# pi3_hat.net
KiCad netlist of a schematic drawn in EAGLE
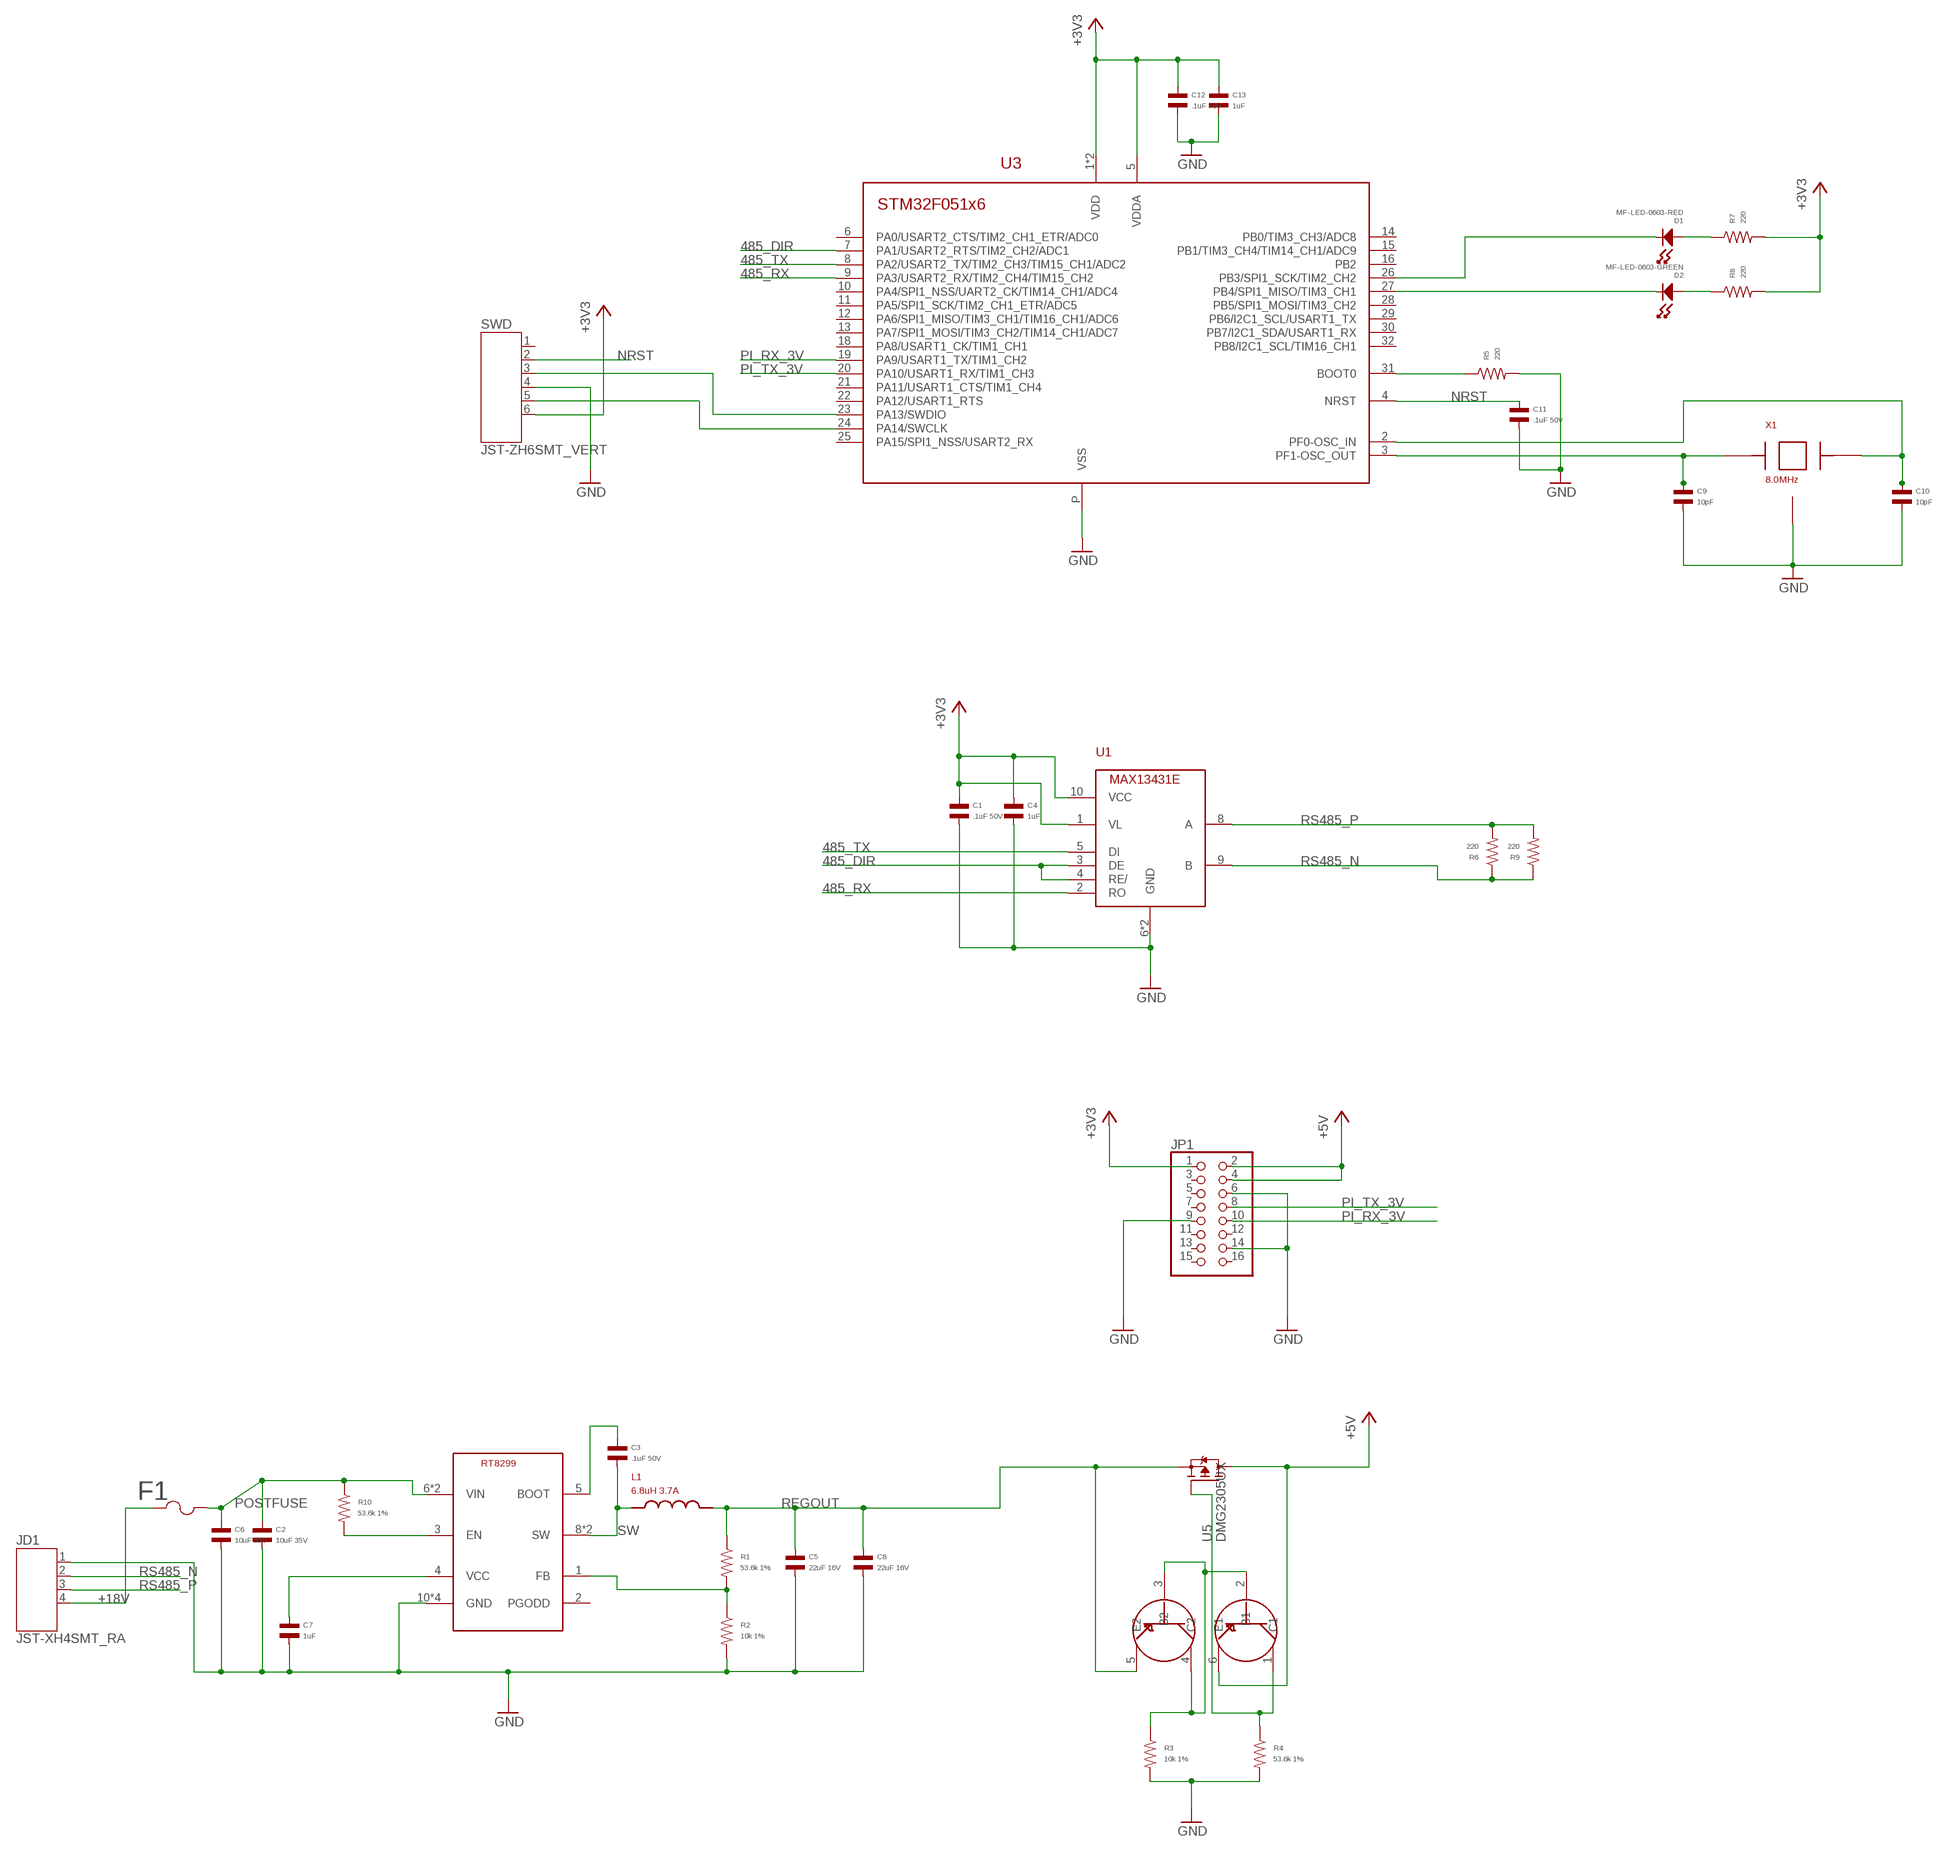
[diagram p0: schematic, sheet 1]

(export (version "E")
  (design (tool "Eeschema 10.0.6"))
  (components
    (comp (ref "C1")
      (value ".1uF 50V")
      (footprint "eagle-import:C0805")
      (fields (field (name "HOUSEPART") "1") (field (name "MPN") "MF-CAP-0805-0.1uF"))
      (libsource (lib "eagle-import") (part "CAPACITOR_NP_0805"))
    )
    (comp (ref "C2")
      (value "10uF 35V")
      (footprint "eagle-import:C1206")
      (fields (field (name "MF") "TDK") (field (name "MPN") "CGA5L1X7R1V106K160AC"))
      (libsource (lib "eagle-import") (part "CAPACITOR_NP_1206"))
    )
    (comp (ref "C3")
      (value ".1uF 50V")
      (footprint "eagle-import:C0805")
      (fields (field (name "HOUSEPART") "1") (field (name "MPN") "MF-CAP-0805-0.1uF"))
      (libsource (lib "eagle-import") (part "CAPACITOR_NP_0805"))
    )
    (comp (ref "C4")
      (value "1uF")
      (footprint "eagle-import:C0603")
      (fields (field (name "HOUSEPART") "1") (field (name "MPN") "MF-CAP-0603-1uF"))
      (libsource (lib "eagle-import") (part "CAPACITOR_NP_0603"))
    )
    (comp (ref "C5")
      (value "22uF 16V")
      (footprint "eagle-import:C1210")
      (fields (field (name "MF") "SAMSUNG") (field (name "MPN") "CL32A226KOJNNNE"))
      (libsource (lib "eagle-import") (part "CAPACITOR_NP_1210"))
    )
    (comp (ref "C6")
      (value "10uF 35V")
      (footprint "eagle-import:C1206")
      (fields (field (name "MF") "TDK") (field (name "MPN") "CGA5L1X7R1V106K160AC"))
      (libsource (lib "eagle-import") (part "CAPACITOR_NP_1206"))
    )
    (comp (ref "C7")
      (value "1uF")
      (footprint "eagle-import:C0603")
      (fields (field (name "HOUSEPART") "1") (field (name "MPN") "MF-CAP-0603-1uF"))
      (libsource (lib "eagle-import") (part "CAPACITOR_NP_0603"))
    )
    (comp (ref "C8")
      (value "22uF 16V")
      (footprint "eagle-import:C1210")
      (fields (field (name "MF") "SAMSUNG") (field (name "MPN") "CL32A226KOJNNNE"))
      (libsource (lib "eagle-import") (part "CAPACITOR_NP_1210"))
    )
    (comp (ref "C9")
      (value "10pF")
      (footprint "eagle-import:C0603")
      (fields
        (field (name "HOUSEPART") "1")
        (field (name "MF") "MACROFAB")
        (field (name "MPN") "MF-CAP-0603-10pF")
      )
      (libsource (lib "eagle-import") (part "CAPACITOR_NP_0603"))
    )
    (comp (ref "C10")
      (value "10pF")
      (footprint "eagle-import:C0603")
      (fields
        (field (name "HOUSEPART") "1")
        (field (name "MF") "MACROFAB")
        (field (name "MPN") "MF-CAP-0603-10pF")
      )
      (libsource (lib "eagle-import") (part "CAPACITOR_NP_0603"))
    )
    (comp (ref "C11")
      (value ".1uF 50V")
      (footprint "eagle-import:C0805")
      (fields (field (name "HOUSEPART") "1") (field (name "MPN") "MF-CAP-0805-0.1uF"))
      (libsource (lib "eagle-import") (part "CAPACITOR_NP_0805"))
    )
    (comp (ref "C12")
      (value ".1uF 50V")
      (footprint "eagle-import:C0805")
      (fields (field (name "HOUSEPART") "1") (field (name "MPN") "MF-CAP-0805-0.1uF"))
      (libsource (lib "eagle-import") (part "CAPACITOR_NP_0805"))
    )
    (comp (ref "C13")
      (value "1uF")
      (footprint "eagle-import:C0603")
      (fields (field (name "HOUSEPART") "1") (field (name "MPN") "MF-CAP-0603-1uF"))
      (libsource (lib "eagle-import") (part "CAPACITOR_NP_0603"))
    )
    (comp (ref "D1")
      (value "MF-LED-0603-RED")
      (footprint "eagle-import:LED0603")
      (fields (field (name "HOUSEPART") "YES"))
      (libsource (lib "eagle-import") (part "LED_SINGLE-0603-RED"))
    )
    (comp (ref "D2")
      (value "MF-LED-0603-GREEN")
      (footprint "eagle-import:LED0603")
      (fields (field (name "HOUSEPART") "YES"))
      (libsource (lib "eagle-import") (part "LED_SINGLE-0603-GREEN"))
    )
    (comp (ref "F1")
      (value "MFU0603FF04000P100")
      (footprint "eagle-import:FUS_VISHAY_MFU0603")
      (libsource (lib "eagle-import") (part "MFU0603FF04000P100"))
    )
    (comp (ref "JD1")
      (value "JST-XH4SMT_RA")
      (footprint "eagle-import:JST_XH_SMT_RA_4")
      (fields (field (name "MF") "JST") (field (name "MPN") "S4B-XH-SM4-TB(LF)(SN)"))
      (libsource (lib "eagle-import") (part "JST-XH4SMT_RA"))
    )
    (comp (ref "JP1")
      (value "PINHD-2X8")
      (footprint "eagle-import:2X08")
      (libsource (lib "eagle-import") (part "PINHD-2X8"))
    )
    (comp (ref "L1")
      (value "6.8uH 3.7A")
      (footprint "eagle-import:TAIYO_8040")
      (fields
        (field (name "HOUSEPART") "0")
        (field (name "MF") "TAIYO YUDEN")
        (field (name "MPN") "NR8040T6R8N")
      )
      (libsource (lib "eagle-import") (part "INDUCTORTAIYO_8040"))
    )
    (comp (ref "R1")
      (value "53.6k 1%")
      (footprint "eagle-import:R0603")
      (fields (field (name "MF") "Panasonic") (field (name "MPN") "ERJ-3EKF5362V"))
      (libsource (lib "eagle-import") (part "RESISTOR_0603"))
    )
    (comp (ref "R2")
      (value "10k 1%")
      (footprint "eagle-import:R0603")
      (fields (field (name "MF") "Panasonic") (field (name "MPN") "ERJ-3EKF1002V"))
      (libsource (lib "eagle-import") (part "RESISTOR_0603"))
    )
    (comp (ref "R3")
      (value "10k 1%")
      (footprint "eagle-import:R0603")
      (fields (field (name "MF") "Panasonic") (field (name "MPN") "ERJ-3EKF1002V"))
      (libsource (lib "eagle-import") (part "RESISTOR_0603"))
    )
    (comp (ref "R4")
      (value "53.6k 1%")
      (footprint "eagle-import:R0603")
      (fields (field (name "MF") "Panasonic") (field (name "MPN") "ERJ-3EKF5362V"))
      (libsource (lib "eagle-import") (part "RESISTOR_0603"))
    )
    (comp (ref "R5")
      (value "220")
      (footprint "eagle-import:R0603")
      (fields (field (name "MPN") "MF-RES-0603-220"))
      (libsource (lib "eagle-import") (part "RESISTOR_0603"))
    )
    (comp (ref "R6")
      (value "220")
      (footprint "eagle-import:R0603")
      (fields (field (name "MPN") "MF-RES-0603-220"))
      (libsource (lib "eagle-import") (part "RESISTOR_0603"))
    )
    (comp (ref "R7")
      (value "220")
      (footprint "eagle-import:R0603")
      (fields (field (name "MPN") "MF-RES-0603-220"))
      (libsource (lib "eagle-import") (part "RESISTOR_0603"))
    )
    (comp (ref "R8")
      (value "220")
      (footprint "eagle-import:R0603")
      (fields (field (name "MPN") "MF-RES-0603-220"))
      (libsource (lib "eagle-import") (part "RESISTOR_0603"))
    )
    (comp (ref "R9")
      (value "220")
      (footprint "eagle-import:R0603")
      (fields (field (name "MPN") "MF-RES-0603-220"))
      (libsource (lib "eagle-import") (part "RESISTOR_0603"))
    )
    (comp (ref "R10")
      (value "53.6k 1%")
      (footprint "eagle-import:R0603")
      (fields (field (name "MF") "Panasonic") (field (name "MPN") "ERJ-3EKF5362V"))
      (libsource (lib "eagle-import") (part "RESISTOR_0603"))
    )
    (comp (ref "SWD")
      (value "JST-ZH6SMT_VERT")
      (footprint "eagle-import:JST_B6B-ZR-SM4-TF(LF)(SN)")
      (fields (field (name "MF") "JST") (field (name "MPN") "B6B-ZR-SM4-TF(LF)(SN)"))
      (libsource (lib "eagle-import") (part "JST-ZH6SMT_VERT"))
    )
    (comp (ref "U1")
      (value "MAX13431E")
      (footprint "eagle-import:TDFN10")
      (fields (field (name "MF") "Maxim") (field (name "MPN") "MAX13431EETB+T"))
      (libsource (lib "eagle-import") (part "MAX13431E"))
    )
    (comp (ref "U2")
      (value "RT829910L_DFN")
      (footprint "eagle-import:10L_DFN")
      (fields (field (name "MF") "Richtek") (field (name "MPN") "RT8299ZQW"))
      (libsource (lib "eagle-import") (part "RT829910L_DFN"))
    )
    (comp (ref "U3")
      (value "STM32F051X6UFQFPN32")
      (footprint "eagle-import:UFQFPN32")
      (fields (field (name "MF") "STMicroelectronics") (field (name "MPN") "STM32F051K6U6"))
      (libsource (lib "eagle-import") (part "STM32F051X6UFQFPN32"))
    )
    (comp (ref "U4")
      (value "DMMT5401")
      (footprint "eagle-import:SOT26")
      (fields (field (name "MF") "Didoes Incorporated") (field (name "MPN") "DMMT5401-7-F"))
      (libsource (lib "eagle-import") (part "DMMT5401"))
    )
    (comp (ref "U5")
      (value "DMG2305UX")
      (footprint "eagle-import:SOT23")
      (fields (field (name "MF") "Diodes Incorporated") (field (name "MPN") "DMG2305UX-13"))
      (libsource (lib "eagle-import") (part "DMG2305UX"))
    )
    (comp (ref "X1")
      (value "8.0MHz")
      (footprint "eagle-import:ABM3B")
      (fields (field (name "MF") "Abracon") (field (name "MPN") "ABM3B-8.000MHZ-10-1-U-T"))
      (libsource (lib "eagle-import") (part "CRYSTALABM3B"))
    )
  )
  (nets
    (net (code "1") (name "+3V3") (class "Default")
      (node (ref "C1") (pin "P$1") (pinfunction "P$1_P$1") (pintype "passive"))
      (node (ref "C12") (pin "P$1") (pinfunction "P$1_P$1") (pintype "passive"))
      (node (ref "C13") (pin "P$1") (pinfunction "P$1_P$1") (pintype "passive"))
      (node (ref "C4") (pin "P$1") (pinfunction "P$1_P$1") (pintype "passive"))
      (node (ref "JP1") (pin "1") (pinfunction "1_1") (pintype "passive"))
      (node (ref "R7") (pin "P$2") (pinfunction "P$2_P$2") (pintype "passive"))
      (node (ref "R8") (pin "P$2") (pinfunction "P$2_P$2") (pintype "passive"))
      (node (ref "SWD") (pin "6") (pinfunction "6_6") (pintype "passive"))
      (node (ref "U1") (pin "1") (pinfunction "VL_1") (pintype "bidirectional"))
      (node (ref "U1") (pin "10") (pinfunction "VCC_10") (pintype "bidirectional"))
      (node (ref "U3") (pin "1") (pinfunction "VDD_1") (pintype "bidirectional"))
      (node (ref "U3") (pin "17") (pinfunction "VDD_17") (pintype "bidirectional"))
      (node (ref "U3") (pin "5") (pinfunction "VDDA_5") (pintype "bidirectional"))
    )
    (net (code "2") (name "+5V") (class "Default")
      (node (ref "JP1") (pin "2") (pinfunction "2_2") (pintype "passive"))
      (node (ref "JP1") (pin "4") (pinfunction "4_4") (pintype "passive"))
      (node (ref "U4") (pin "6") (pinfunction "E1_6") (pintype "bidirectional"))
      (node (ref "U5") (pin "3") (pinfunction "D_3") (pintype "passive"))
    )
    (net (code "3") (name "/+18V") (class "Default")
      (node (ref "F1") (pin "1") (pinfunction "1_1") (pintype "passive"))
      (node (ref "JD1") (pin "4") (pinfunction "4_4") (pintype "passive"))
    )
    (net (code "4") (name "/485_DIR") (class "Default")
      (node (ref "U1") (pin "3") (pinfunction "DE_3") (pintype "bidirectional"))
      (node (ref "U1") (pin "4") (pinfunction "RE/_4") (pintype "bidirectional"))
      (node (ref "U3") (pin "7") (pinfunction "PA1/USART2_RTS/TIM2_CH2/ADC1_7") (pintype "bidirectional"))
    )
    (net (code "5") (name "/485_RX") (class "Default")
      (node (ref "U1") (pin "2") (pinfunction "RO_2") (pintype "bidirectional"))
      (node (ref "U3") (pin "9") (pinfunction "PA3/USART2_RX/TIM2_CH4/TIM15_CH2_9") (pintype "bidirectional"))
    )
    (net (code "6") (name "/485_TX") (class "Default")
      (node (ref "U1") (pin "5") (pinfunction "DI_5") (pintype "bidirectional"))
      (node (ref "U3") (pin "8") (pinfunction "PA2/USART2_TX/TIM2_CH3/TIM15_CH1/ADC2_8") (pintype "bidirectional"))
    )
    (net (code "7") (name "/NRST") (class "Default")
      (node (ref "C11") (pin "P$1") (pinfunction "P$1_P$1") (pintype "passive"))
      (node (ref "SWD") (pin "2") (pinfunction "2_2") (pintype "passive"))
      (node (ref "U3") (pin "4") (pinfunction "NRST_4") (pintype "bidirectional"))
    )
    (net (code "8") (name "/PI_RX_3V") (class "Default")
      (node (ref "JP1") (pin "10") (pinfunction "10_10") (pintype "passive"))
      (node (ref "U3") (pin "19") (pinfunction "PA9/USART1_TX/TIM1_CH2_19") (pintype "bidirectional"))
    )
    (net (code "9") (name "/PI_TX_3V") (class "Default")
      (node (ref "JP1") (pin "8") (pinfunction "8_8") (pintype "passive"))
      (node (ref "U3") (pin "20") (pinfunction "PA10/USART1_RX/TIM1_CH3_20") (pintype "bidirectional"))
    )
    (net (code "10") (name "/POSTFUSE") (class "Default")
      (node (ref "C2") (pin "P$1") (pinfunction "P$1_P$1") (pintype "passive"))
      (node (ref "C6") (pin "P$1") (pinfunction "P$1_P$1") (pintype "passive"))
      (node (ref "F1") (pin "2") (pinfunction "2_2") (pintype "passive"))
      (node (ref "R10") (pin "P$1") (pinfunction "P$1_P$1") (pintype "passive"))
      (node (ref "U2") (pin "6") (pinfunction "VIN_6") (pintype "bidirectional"))
      (node (ref "U2") (pin "7") (pinfunction "VIN_7") (pintype "bidirectional"))
    )
    (net (code "11") (name "/REGOUT") (class "Default")
      (node (ref "C5") (pin "P$1") (pinfunction "P$1_P$1") (pintype "passive"))
      (node (ref "C8") (pin "P$1") (pinfunction "P$1_P$1") (pintype "passive"))
      (node (ref "L1") (pin "2") (pinfunction "P$2_2") (pintype "passive"))
      (node (ref "R1") (pin "P$1") (pinfunction "P$1_P$1") (pintype "passive"))
      (node (ref "U4") (pin "5") (pinfunction "E2_5") (pintype "bidirectional"))
      (node (ref "U5") (pin "2") (pinfunction "S_2") (pintype "passive"))
    )
    (net (code "12") (name "/RS485_N") (class "Default")
      (node (ref "JD1") (pin "2") (pinfunction "2_2") (pintype "passive"))
      (node (ref "R6") (pin "P$1") (pinfunction "P$1_P$1") (pintype "passive"))
      (node (ref "R9") (pin "P$1") (pinfunction "P$1_P$1") (pintype "passive"))
      (node (ref "U1") (pin "9") (pinfunction "B_9") (pintype "bidirectional"))
    )
    (net (code "13") (name "/RS485_P") (class "Default")
      (node (ref "JD1") (pin "3") (pinfunction "3_3") (pintype "passive"))
      (node (ref "R6") (pin "P$2") (pinfunction "P$2_P$2") (pintype "passive"))
      (node (ref "R9") (pin "P$2") (pinfunction "P$2_P$2") (pintype "passive"))
      (node (ref "U1") (pin "8") (pinfunction "A_8") (pintype "bidirectional"))
    )
    (net (code "14") (name "/SW") (class "Default")
      (node (ref "C3") (pin "P$2") (pinfunction "P$2_P$2") (pintype "passive"))
      (node (ref "L1") (pin "1") (pinfunction "P$1_1") (pintype "passive"))
      (node (ref "U2") (pin "8") (pinfunction "SW_8") (pintype "bidirectional"))
      (node (ref "U2") (pin "9") (pinfunction "SW_9") (pintype "bidirectional"))
    )
    (net (code "15") (name "GND") (class "Default")
      (node (ref "C1") (pin "P$2") (pinfunction "P$2_P$2") (pintype "passive"))
      (node (ref "C10") (pin "P$2") (pinfunction "P$2_P$2") (pintype "passive"))
      (node (ref "C11") (pin "P$2") (pinfunction "P$2_P$2") (pintype "passive"))
      (node (ref "C12") (pin "P$2") (pinfunction "P$2_P$2") (pintype "passive"))
      (node (ref "C13") (pin "P$2") (pinfunction "P$2_P$2") (pintype "passive"))
      (node (ref "C2") (pin "P$2") (pinfunction "P$2_P$2") (pintype "passive"))
      (node (ref "C4") (pin "P$2") (pinfunction "P$2_P$2") (pintype "passive"))
      (node (ref "C5") (pin "P$2") (pinfunction "P$2_P$2") (pintype "passive"))
      (node (ref "C6") (pin "P$2") (pinfunction "P$2_P$2") (pintype "passive"))
      (node (ref "C7") (pin "P$2") (pinfunction "P$2_P$2") (pintype "passive"))
      (node (ref "C8") (pin "P$2") (pinfunction "P$2_P$2") (pintype "passive"))
      (node (ref "C9") (pin "P$2") (pinfunction "P$2_P$2") (pintype "passive"))
      (node (ref "JD1") (pin "1") (pinfunction "1_1") (pintype "passive"))
      (node (ref "JP1") (pin "14") (pinfunction "14_14") (pintype "passive"))
      (node (ref "JP1") (pin "6") (pinfunction "6_6") (pintype "passive"))
      (node (ref "JP1") (pin "9") (pinfunction "9_9") (pintype "passive"))
      (node (ref "R2") (pin "P$2") (pinfunction "P$2_P$2") (pintype "passive"))
      (node (ref "R3") (pin "P$2") (pinfunction "P$2_P$2") (pintype "passive"))
      (node (ref "R4") (pin "P$2") (pinfunction "P$2_P$2") (pintype "passive"))
      (node (ref "R5") (pin "P$2") (pinfunction "P$2_P$2") (pintype "passive"))
      (node (ref "SWD") (pin "4") (pinfunction "4_4") (pintype "passive"))
      (node (ref "U1") (pin "6") (pinfunction "GND_6") (pintype "bidirectional"))
      (node (ref "U1") (pin "PAD") (pinfunction "GND_PAD") (pintype "bidirectional"))
      (node (ref "U2") (pin "10") (pinfunction "GND_10") (pintype "bidirectional"))
      (node (ref "U2") (pin "P0") (pinfunction "GND_P0") (pintype "bidirectional"))
      (node (ref "U2") (pin "P1") (pinfunction "GND_P1") (pintype "bidirectional"))
      (node (ref "U2") (pin "P2") (pinfunction "GND_P2") (pintype "bidirectional"))
      (node (ref "U3") (pin "P") (pinfunction "VSS_P") (pintype "bidirectional"))
      (node (ref "X1") (pin "2") (pinfunction "P$3_2") (pintype "bidirectional"))
      (node (ref "X1") (pin "4") (pinfunction "P$3_4") (pintype "bidirectional"))
    )
    (net (code "16") (name "Net-(D1-PadANODE)") (class "Default")
      (node (ref "D1") (pin "ANODE") (pinfunction "ANODE_ANODE") (pintype "power_in"))
      (node (ref "R7") (pin "P$1") (pinfunction "P$1_P$1") (pintype "passive"))
    )
    (net (code "17") (name "Net-(D2-PadANODE)") (class "Default")
      (node (ref "D2") (pin "ANODE") (pinfunction "ANODE_ANODE") (pintype "power_in"))
      (node (ref "R8") (pin "P$1") (pinfunction "P$1_P$1") (pintype "passive"))
    )
    (net (code "18") (name "Net-(U2-BOOT)") (class "Default")
      (node (ref "C3") (pin "P$1") (pinfunction "P$1_P$1") (pintype "passive"))
      (node (ref "U2") (pin "5") (pinfunction "BOOT_5") (pintype "bidirectional"))
    )
    (net (code "19") (name "Net-(U2-EN)") (class "Default")
      (node (ref "R10") (pin "P$2") (pinfunction "P$2_P$2") (pintype "passive"))
      (node (ref "U2") (pin "3") (pinfunction "EN_3") (pintype "bidirectional"))
    )
    (net (code "20") (name "Net-(U2-FB)") (class "Default")
      (node (ref "R1") (pin "P$2") (pinfunction "P$2_P$2") (pintype "passive"))
      (node (ref "R2") (pin "P$1") (pinfunction "P$1_P$1") (pintype "passive"))
      (node (ref "U2") (pin "1") (pinfunction "FB_1") (pintype "bidirectional"))
    )
    (net (code "21") (name "Net-(U2-VCC)") (class "Default")
      (node (ref "C7") (pin "P$1") (pinfunction "P$1_P$1") (pintype "passive"))
      (node (ref "U2") (pin "4") (pinfunction "VCC_4") (pintype "bidirectional"))
    )
    (net (code "22") (name "Net-(U3-BOOT0)") (class "Default")
      (node (ref "R5") (pin "P$1") (pinfunction "P$1_P$1") (pintype "passive"))
      (node (ref "U3") (pin "31") (pinfunction "BOOT0_31") (pintype "bidirectional"))
    )
    (net (code "23") (name "Net-(U3-PA13{slash}SWDIO)") (class "Default")
      (node (ref "SWD") (pin "3") (pinfunction "3_3") (pintype "passive"))
      (node (ref "U3") (pin "23") (pinfunction "PA13/SWDIO_23") (pintype "bidirectional"))
    )
    (net (code "24") (name "Net-(U3-PA14{slash}SWCLK)") (class "Default")
      (node (ref "SWD") (pin "5") (pinfunction "5_5") (pintype "passive"))
      (node (ref "U3") (pin "24") (pinfunction "PA14/SWCLK_24") (pintype "bidirectional"))
    )
    (net (code "25") (name "Net-(U3-PB3{slash}SPI1_SCK{slash}TIM2_CH2)") (class "Default")
      (node (ref "D1") (pin "CATHODE") (pinfunction "CATHODE_CATHODE") (pintype "power_in"))
      (node (ref "U3") (pin "26") (pinfunction "PB3/SPI1_SCK/TIM2_CH2_26") (pintype "bidirectional"))
    )
    (net (code "26") (name "Net-(U3-PB4{slash}SPI1_MISO{slash}TIM3_CH1)") (class "Default")
      (node (ref "D2") (pin "CATHODE") (pinfunction "CATHODE_CATHODE") (pintype "power_in"))
      (node (ref "U3") (pin "27") (pinfunction "PB4/SPI1_MISO/TIM3_CH1_27") (pintype "bidirectional"))
    )
    (net (code "27") (name "Net-(U3-PF0-OSC_IN)") (class "Default")
      (node (ref "C10") (pin "P$1") (pinfunction "P$1_P$1") (pintype "passive"))
      (node (ref "U3") (pin "2") (pinfunction "PF0-OSC_IN_2") (pintype "bidirectional"))
      (node (ref "X1") (pin "3") (pinfunction "P$2_3") (pintype "bidirectional"))
    )
    (net (code "28") (name "Net-(U3-PF1-OSC_OUT)") (class "Default")
      (node (ref "C9") (pin "P$1") (pinfunction "P$1_P$1") (pintype "passive"))
      (node (ref "U3") (pin "3") (pinfunction "PF1-OSC_OUT_3") (pintype "bidirectional"))
      (node (ref "X1") (pin "1") (pinfunction "P$1_1") (pintype "bidirectional"))
    )
    (net (code "29") (name "Net-(U4-B1)") (class "Default")
      (node (ref "R3") (pin "P$1") (pinfunction "P$1_P$1") (pintype "passive"))
      (node (ref "U4") (pin "2") (pinfunction "B1_2") (pintype "bidirectional"))
      (node (ref "U4") (pin "3") (pinfunction "B2_3") (pintype "bidirectional"))
      (node (ref "U4") (pin "4") (pinfunction "C2_4") (pintype "bidirectional"))
    )
    (net (code "30") (name "Net-(U4-C1)") (class "Default")
      (node (ref "R4") (pin "P$1") (pinfunction "P$1_P$1") (pintype "passive"))
      (node (ref "U4") (pin "1") (pinfunction "C1_1") (pintype "bidirectional"))
      (node (ref "U5") (pin "1") (pinfunction "G_1") (pintype "passive"))
    )
    (net (code "31") (name "unconnected-(JP1-Pad3)") (class "Default")
      (node (ref "JP1") (pin "3") (pinfunction "3_3") (pintype "passive"))
    )
    (net (code "32") (name "unconnected-(JP1-Pad5)") (class "Default")
      (node (ref "JP1") (pin "5") (pinfunction "5_5") (pintype "passive"))
    )
    (net (code "33") (name "unconnected-(JP1-Pad7)") (class "Default")
      (node (ref "JP1") (pin "7") (pinfunction "7_7") (pintype "passive"))
    )
    (net (code "34") (name "unconnected-(JP1-Pad11)") (class "Default")
      (node (ref "JP1") (pin "11") (pinfunction "11_11") (pintype "passive"))
    )
    (net (code "35") (name "unconnected-(JP1-Pad12)") (class "Default")
      (node (ref "JP1") (pin "12") (pinfunction "12_12") (pintype "passive"))
    )
    (net (code "36") (name "unconnected-(JP1-Pad13)") (class "Default")
      (node (ref "JP1") (pin "13") (pinfunction "13_13") (pintype "passive"))
    )
    (net (code "37") (name "unconnected-(JP1-Pad15)") (class "Default")
      (node (ref "JP1") (pin "15") (pinfunction "15_15") (pintype "passive"))
    )
    (net (code "38") (name "unconnected-(JP1-Pad16)") (class "Default")
      (node (ref "JP1") (pin "16") (pinfunction "16_16") (pintype "passive"))
    )
    (net (code "39") (name "unconnected-(SWD-Pad1)") (class "Default")
      (node (ref "SWD") (pin "1") (pinfunction "1_1") (pintype "passive"))
    )
    (net (code "40") (name "unconnected-(U2-PGODD-Pad2)") (class "Default")
      (node (ref "U2") (pin "2") (pinfunction "PGODD_2") (pintype "bidirectional"))
    )
    (net (code "41") (name "unconnected-(U3-PA0{slash}USART2_CTS{slash}TIM2_CH1_ETR{slash}ADC0-Pad6)") (class "Default")
      (node (ref "U3") (pin "6") (pinfunction "PA0/USART2_CTS/TIM2_CH1_ETR/ADC0_6") (pintype "bidirectional"))
    )
    (net (code "42") (name "unconnected-(U3-PA4{slash}SPI1_NSS{slash}UART2_CK{slash}TIM14_CH1{slash}ADC4-Pad10)") (class "Default")
      (node (ref "U3") (pin "10") (pinfunction "PA4/SPI1_NSS/UART2_CK/TIM14_CH1/ADC4_10") (pintype "bidirectional"))
    )
    (net (code "43") (name "unconnected-(U3-PA5{slash}SPI1_SCK{slash}TIM2_CH1_ETR{slash}ADC5-Pad11)") (class "Default")
      (node (ref "U3") (pin "11") (pinfunction "PA5/SPI1_SCK/TIM2_CH1_ETR/ADC5_11") (pintype "bidirectional"))
    )
    (net (code "44") (name "unconnected-(U3-PA6{slash}SPI1_MISO{slash}TIM3_CH1{slash}TIM16_CH1{slash}ADC6-Pad12)") (class "Default")
      (node (ref "U3") (pin "12") (pinfunction "PA6/SPI1_MISO/TIM3_CH1/TIM16_CH1/ADC6_12") (pintype "bidirectional"))
    )
    (net (code "45") (name "unconnected-(U3-PA7{slash}SPI1_MOSI{slash}TIM3_CH2{slash}TIM14_CH1{slash}ADC7-Pad13)") (class "Default")
      (node (ref "U3") (pin "13") (pinfunction "PA7/SPI1_MOSI/TIM3_CH2/TIM14_CH1/ADC7_13") (pintype "bidirectional"))
    )
    (net (code "46") (name "unconnected-(U3-PA8{slash}USART1_CK{slash}TIM1_CH1-Pad18)") (class "Default")
      (node (ref "U3") (pin "18") (pinfunction "PA8/USART1_CK/TIM1_CH1_18") (pintype "bidirectional"))
    )
    (net (code "47") (name "unconnected-(U3-PA11{slash}USART1_CTS{slash}TIM1_CH4-Pad21)") (class "Default")
      (node (ref "U3") (pin "21") (pinfunction "PA11/USART1_CTS/TIM1_CH4_21") (pintype "bidirectional"))
    )
    (net (code "48") (name "unconnected-(U3-PA12{slash}USART1_RTS-Pad22)") (class "Default")
      (node (ref "U3") (pin "22") (pinfunction "PA12/USART1_RTS_22") (pintype "bidirectional"))
    )
    (net (code "49") (name "unconnected-(U3-PA15{slash}SPI1_NSS{slash}USART2_RX-Pad25)") (class "Default")
      (node (ref "U3") (pin "25") (pinfunction "PA15/SPI1_NSS/USART2_RX_25") (pintype "bidirectional"))
    )
    (net (code "50") (name "unconnected-(U3-PB0{slash}TIM3_CH3{slash}ADC8-Pad14)") (class "Default")
      (node (ref "U3") (pin "14") (pinfunction "PB0/TIM3_CH3/ADC8_14") (pintype "bidirectional"))
    )
    (net (code "51") (name "unconnected-(U3-PB1{slash}TIM3_CH4{slash}TIM14_CH1{slash}ADC9-Pad15)") (class "Default")
      (node (ref "U3") (pin "15") (pinfunction "PB1/TIM3_CH4/TIM14_CH1/ADC9_15") (pintype "bidirectional"))
    )
    (net (code "52") (name "unconnected-(U3-PB2-Pad16)") (class "Default")
      (node (ref "U3") (pin "16") (pinfunction "PB2_16") (pintype "bidirectional"))
    )
    (net (code "53") (name "unconnected-(U3-PB5{slash}SPI1_MOSI{slash}TIM3_CH2-Pad28)") (class "Default")
      (node (ref "U3") (pin "28") (pinfunction "PB5/SPI1_MOSI/TIM3_CH2_28") (pintype "bidirectional"))
    )
    (net (code "54") (name "unconnected-(U3-PB6{slash}I2C1_SCL{slash}USART1_TX-Pad29)") (class "Default")
      (node (ref "U3") (pin "29") (pinfunction "PB6/I2C1_SCL/USART1_TX_29") (pintype "bidirectional"))
    )
    (net (code "55") (name "unconnected-(U3-PB7{slash}I2C1_SDA{slash}USART1_RX-Pad30)") (class "Default")
      (node (ref "U3") (pin "30") (pinfunction "PB7/I2C1_SDA/USART1_RX_30") (pintype "bidirectional"))
    )
    (net (code "56") (name "unconnected-(U3-PB8{slash}I2C1_SCL{slash}TIM16_CH1-Pad32)") (class "Default")
      (node (ref "U3") (pin "32") (pinfunction "PB8/I2C1_SCL/TIM16_CH1_32") (pintype "bidirectional"))
    )
  )
)
